# usbboarduino20.net
KiCad netlist of a schematic drawn in EAGLE
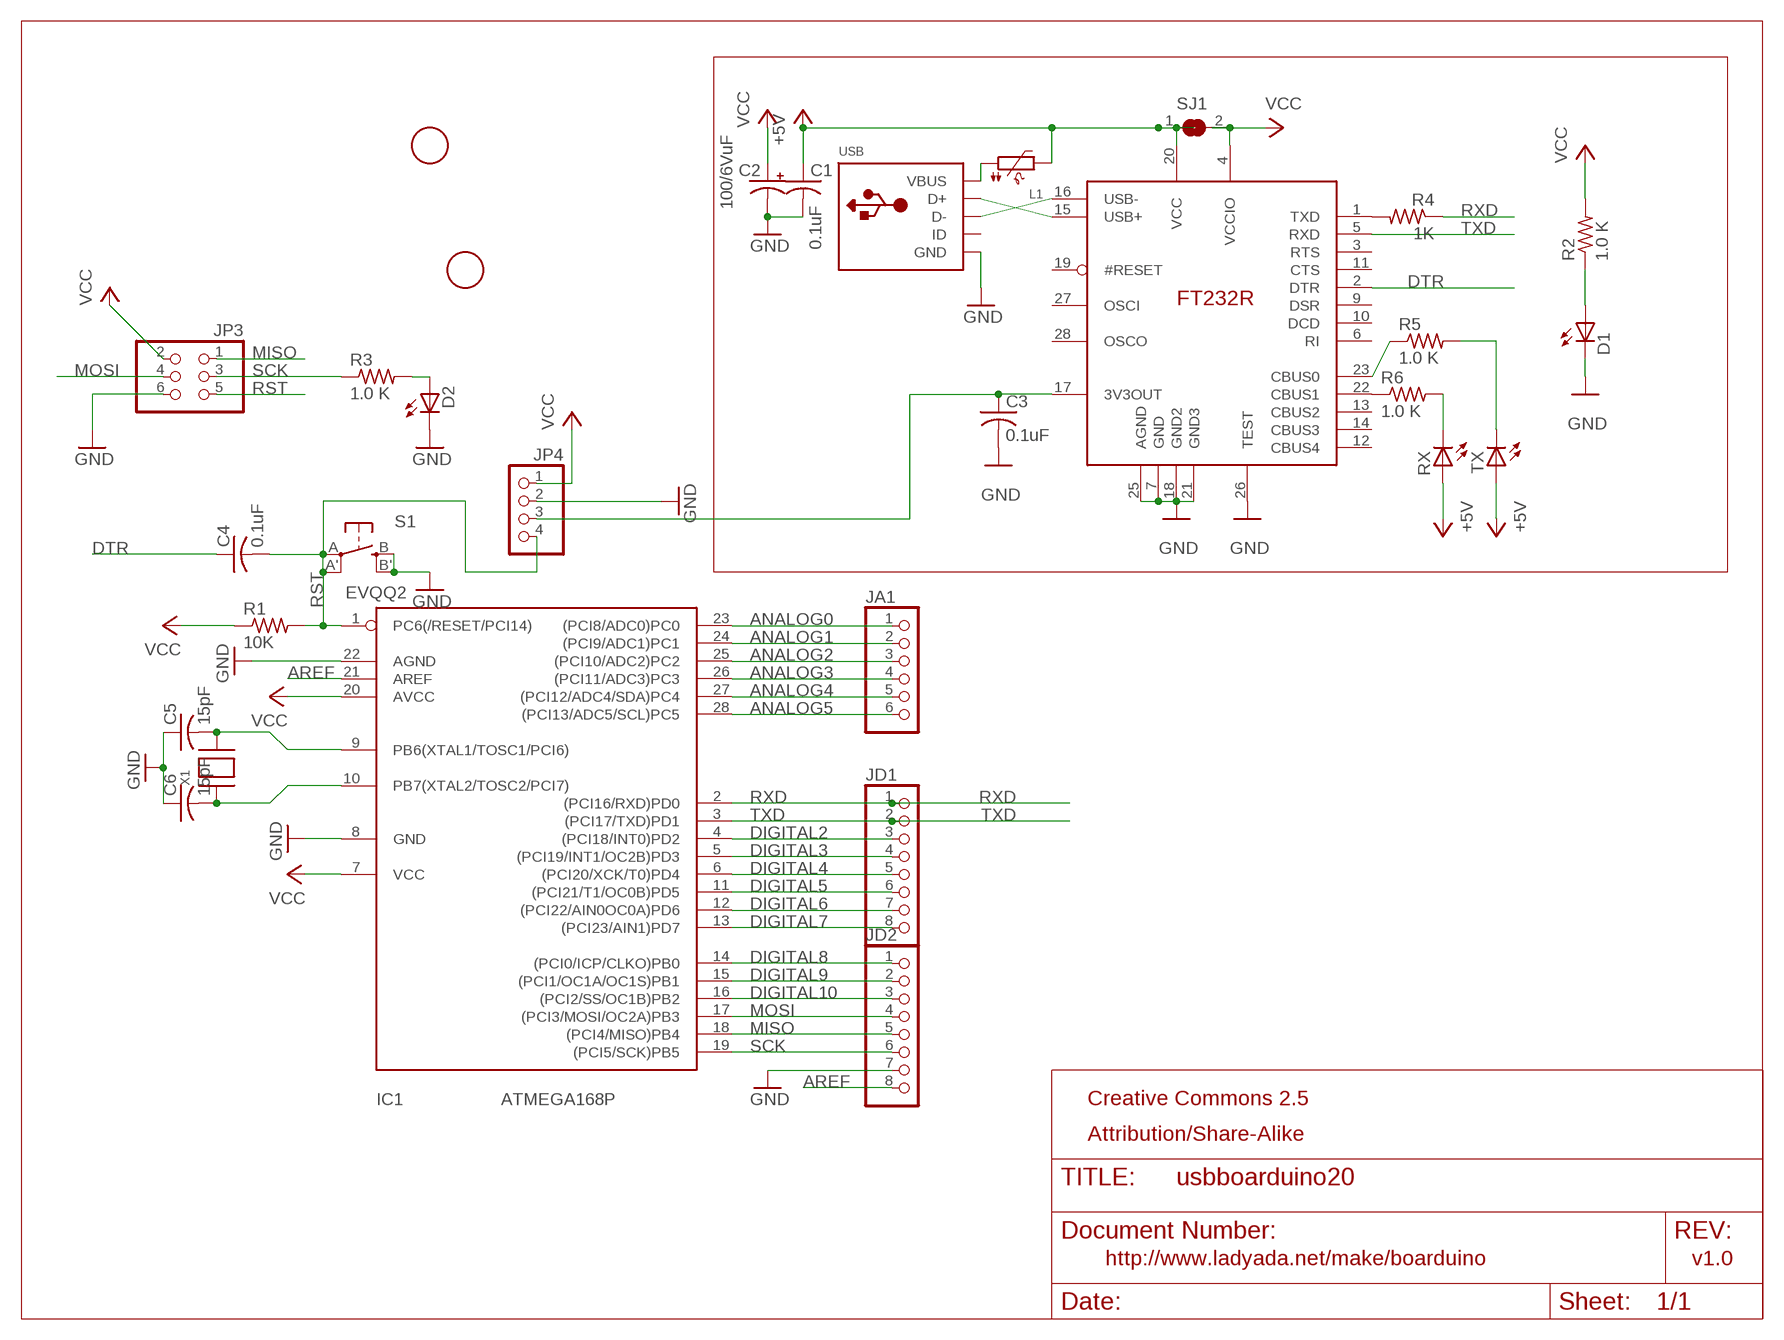
[diagram p0: schematic, sheet 1]

(export (version "E")
  (design (tool "Eeschema 10.0.6"))
  (components
    (comp (ref "C1")
      (value "0.1uF")
      (footprint "eagle-import:C0805K")
      (libsource (lib "eagle-import") (part "C-USC0805K"))
    )
    (comp (ref "C2")
      (value "100/6VuF")
      (footprint "eagle-import:B_3528-21R")
      (libsource (lib "eagle-import") (part "CPOL-USB/3528-21R"))
    )
    (comp (ref "C3")
      (value "0.1uF")
      (footprint "eagle-import:C0805K")
      (libsource (lib "eagle-import") (part "C-USC0805K"))
    )
    (comp (ref "C4")
      (value "0.1uF")
      (footprint "eagle-import:C0805K")
      (libsource (lib "eagle-import") (part "C-USC0805K"))
    )
    (comp (ref "C5")
      (value "15pF")
      (footprint "eagle-import:C0805K")
      (libsource (lib "eagle-import") (part "C-USC0805K"))
    )
    (comp (ref "C6")
      (value "15pF")
      (footprint "eagle-import:C0805K")
      (libsource (lib "eagle-import") (part "C-USC0805K"))
    )
    (comp (ref "D1")
      (value "LEDCHIPLED_0805")
      (footprint "eagle-import:CHIPLED_0805")
      (libsource (lib "eagle-import") (part "LEDCHIPLED_0805"))
    )
    (comp (ref "D2")
      (value "Green")
      (footprint "eagle-import:CHIPLED_0805")
      (libsource (lib "eagle-import") (part "LEDCHIPLED_0805"))
    )
    (comp (ref "IC1")
      (value "ATMEGA168P")
      (footprint "eagle-import:DIL28_3")
      (libsource (lib "eagle-import") (part "ATMEGA168PROUND"))
    )
    (comp (ref "IC2")
      (value "FT232R")
      (footprint "eagle-import:TSSOP28")
      (libsource (lib "eagle-import") (part "FT232R"))
    )
    (comp (ref "JA1")
      (value "PINHD-1X6CB")
      (footprint "eagle-import:1X06-CLEANBIG")
      (libsource (lib "eagle-import") (part "PINHD-1X6CB"))
    )
    (comp (ref "JD1")
      (value "PINHD-1X8CLEANBIG")
      (footprint "eagle-import:1X08-CLEANBIG")
      (libsource (lib "eagle-import") (part "PINHD-1X8CLEANBIG"))
    )
    (comp (ref "JD2")
      (value "PINHD-1X8CLEANBIG")
      (footprint "eagle-import:1X08-CLEANBIG")
      (libsource (lib "eagle-import") (part "PINHD-1X8CLEANBIG"))
    )
    (comp (ref "JP3")
      (value "PINHD-2X3")
      (footprint "eagle-import:2X03")
      (libsource (lib "eagle-import") (part "PINHD-2X3"))
    )
    (comp (ref "JP4")
      (value "PINHD-1X4CB")
      (footprint "eagle-import:1X04-CB")
      (libsource (lib "eagle-import") (part "PINHD-1X4CB"))
    )
    (comp (ref "L1")
      (value "PTC1206")
      (footprint "eagle-import:1206")
      (libsource (lib "eagle-import") (part "PTC1206"))
    )
    (comp (ref "R1")
      (value "10K")
      (footprint "eagle-import:R0805")
      (libsource (lib "eagle-import") (part "R-US_R0805"))
    )
    (comp (ref "R2")
      (value "1.0 K")
      (footprint "eagle-import:R0805")
      (libsource (lib "eagle-import") (part "R-US_R0805"))
    )
    (comp (ref "R3")
      (value "1.0 K")
      (footprint "eagle-import:R0805")
      (libsource (lib "eagle-import") (part "R-US_R0805"))
    )
    (comp (ref "R4")
      (value "1K")
      (footprint "eagle-import:R0805")
      (libsource (lib "eagle-import") (part "R-US_R0805"))
    )
    (comp (ref "R5")
      (value "1.0 K")
      (footprint "eagle-import:R0805")
      (libsource (lib "eagle-import") (part "R-US_R0805"))
    )
    (comp (ref "R6")
      (value "1.0 K")
      (footprint "eagle-import:R0805")
      (libsource (lib "eagle-import") (part "R-US_R0805"))
    )
    (comp (ref "RX")
      (value "Green")
      (footprint "eagle-import:CHIPLED_0805")
      (libsource (lib "eagle-import") (part "LEDCHIPLED_0805"))
    )
    (comp (ref "S1")
      (value "EVQQ2")
      (footprint "eagle-import:EVQ-Q2")
      (libsource (lib "eagle-import") (part "EVQQ2"))
    )
    (comp (ref "SJ1")
      (value "SOLDERJUMPERREFLOW")
      (footprint "eagle-import:SOLDERJUMPER_REFLOW")
      (libsource (lib "eagle-import") (part "SOLDERJUMPERREFLOW"))
    )
    (comp (ref "TX")
      (value "Green")
      (footprint "eagle-import:CHIPLED_0805")
      (libsource (lib "eagle-import") (part "LEDCHIPLED_0805"))
    )
    (comp (ref "U$1")
      (value "FIDUCIAL")
      (footprint "eagle-import:FIDUCIAL_1MM")
      (libsource (lib "eagle-import") (part "FIDUCIAL"))
    )
    (comp (ref "U$2")
      (value "FIDUCIAL")
      (footprint "eagle-import:FIDUCIAL_1MM")
      (libsource (lib "eagle-import") (part "FIDUCIAL"))
    )
    (comp (ref "USB")
      (value "USBMINIB")
      (footprint "eagle-import:USB-MINIB")
      (libsource (lib "eagle-import") (part "USBMINIB"))
    )
    (comp (ref "X1")
      (value "XTALNX5032")
      (footprint "eagle-import:NX5032")
      (libsource (lib "eagle-import") (part "XTALNX5032"))
    )
  )
  (nets
    (net (code "1") (name "+5V") (class "Default")
      (node (ref "C1") (pin "1") (pinfunction "1_1") (pintype "passive"))
      (node (ref "IC2") (pin "20") (pinfunction "VCC_20") (pintype "power_in"))
      (node (ref "L1") (pin "2") (pinfunction "2_2") (pintype "passive"))
      (node (ref "RX") (pin "A") (pinfunction "A_A") (pintype "passive"))
      (node (ref "SJ1") (pin "1") (pinfunction "1_1") (pintype "passive"))
      (node (ref "TX") (pin "A") (pinfunction "A_A") (pintype "passive"))
    )
    (net (code "2") (name "/ANALOG0") (class "Default")
      (node (ref "IC1") (pin "23") (pinfunction "(PCI8/ADC0)PC0_23") (pintype "bidirectional"))
      (node (ref "JA1") (pin "1") (pinfunction "1_1") (pintype "passive"))
    )
    (net (code "3") (name "/ANALOG1") (class "Default")
      (node (ref "IC1") (pin "24") (pinfunction "(PCI9/ADC1)PC1_24") (pintype "bidirectional"))
      (node (ref "JA1") (pin "2") (pinfunction "2_2") (pintype "passive"))
    )
    (net (code "4") (name "/ANALOG2") (class "Default")
      (node (ref "IC1") (pin "25") (pinfunction "(PCI10/ADC2)PC2_25") (pintype "bidirectional"))
      (node (ref "JA1") (pin "3") (pinfunction "3_3") (pintype "passive"))
    )
    (net (code "5") (name "/ANALOG3") (class "Default")
      (node (ref "IC1") (pin "26") (pinfunction "(PCI11/ADC3)PC3_26") (pintype "bidirectional"))
      (node (ref "JA1") (pin "4") (pinfunction "4_4") (pintype "passive"))
    )
    (net (code "6") (name "/ANALOG4") (class "Default")
      (node (ref "IC1") (pin "27") (pinfunction "(PCI12/ADC4/SDA)PC4_27") (pintype "bidirectional"))
      (node (ref "JA1") (pin "5") (pinfunction "5_5") (pintype "passive"))
    )
    (net (code "7") (name "/ANALOG5") (class "Default")
      (node (ref "IC1") (pin "28") (pinfunction "(PCI13/ADC5/SCL)PC5_28") (pintype "bidirectional"))
      (node (ref "JA1") (pin "6") (pinfunction "6_6") (pintype "passive"))
    )
    (net (code "8") (name "/AREF") (class "Default")
      (node (ref "IC1") (pin "21") (pinfunction "AREF_21") (pintype "bidirectional"))
      (node (ref "JD2") (pin "8") (pinfunction "8_8") (pintype "passive"))
    )
    (net (code "9") (name "/DIGITAL2") (class "Default")
      (node (ref "IC1") (pin "4") (pinfunction "(PCI18/INT0)PD2_4") (pintype "bidirectional"))
      (node (ref "JD1") (pin "3") (pinfunction "3_3") (pintype "passive"))
    )
    (net (code "10") (name "/DIGITAL3") (class "Default")
      (node (ref "IC1") (pin "5") (pinfunction "(PCI19/INT1/OC2B)PD3_5") (pintype "bidirectional"))
      (node (ref "JD1") (pin "4") (pinfunction "4_4") (pintype "passive"))
    )
    (net (code "11") (name "/DIGITAL4") (class "Default")
      (node (ref "IC1") (pin "6") (pinfunction "(PCI20/XCK/T0)PD4_6") (pintype "bidirectional"))
      (node (ref "JD1") (pin "5") (pinfunction "5_5") (pintype "passive"))
    )
    (net (code "12") (name "/DIGITAL5") (class "Default")
      (node (ref "IC1") (pin "11") (pinfunction "(PCI21/T1/OC0B)PD5_11") (pintype "bidirectional"))
      (node (ref "JD1") (pin "6") (pinfunction "6_6") (pintype "passive"))
    )
    (net (code "13") (name "/DIGITAL6") (class "Default")
      (node (ref "IC1") (pin "12") (pinfunction "(PCI22/AIN0OC0A)PD6_12") (pintype "bidirectional"))
      (node (ref "JD1") (pin "7") (pinfunction "7_7") (pintype "passive"))
    )
    (net (code "14") (name "/DIGITAL7") (class "Default")
      (node (ref "IC1") (pin "13") (pinfunction "(PCI23/AIN1)PD7_13") (pintype "bidirectional"))
      (node (ref "JD1") (pin "8") (pinfunction "8_8") (pintype "passive"))
    )
    (net (code "15") (name "/DIGITAL8") (class "Default")
      (node (ref "IC1") (pin "14") (pinfunction "(PCI0/ICP/CLKO)PB0_14") (pintype "bidirectional"))
      (node (ref "JD2") (pin "1") (pinfunction "1_1") (pintype "passive"))
    )
    (net (code "16") (name "/DIGITAL9") (class "Default")
      (node (ref "IC1") (pin "15") (pinfunction "(PCI1/OC1A/OC1S)PB1_15") (pintype "bidirectional"))
      (node (ref "JD2") (pin "2") (pinfunction "2_2") (pintype "passive"))
    )
    (net (code "17") (name "/DIGITAL10") (class "Default")
      (node (ref "IC1") (pin "16") (pinfunction "(PCI2/SS/OC1B)PB2_16") (pintype "bidirectional"))
      (node (ref "JD2") (pin "3") (pinfunction "3_3") (pintype "passive"))
    )
    (net (code "18") (name "/DTR") (class "Default")
      (node (ref "C4") (pin "1") (pinfunction "1_1") (pintype "passive"))
      (node (ref "IC2") (pin "2") (pinfunction "DTR_2") (pintype "output"))
    )
    (net (code "19") (name "/MISO") (class "Default")
      (node (ref "IC1") (pin "18") (pinfunction "(PCI4/MISO)PB4_18") (pintype "bidirectional"))
      (node (ref "JD2") (pin "5") (pinfunction "5_5") (pintype "passive"))
      (node (ref "JP3") (pin "1") (pinfunction "1_1") (pintype "passive"))
    )
    (net (code "20") (name "/MOSI") (class "Default")
      (node (ref "IC1") (pin "17") (pinfunction "(PCI3/MOSI/OC2A)PB3_17") (pintype "bidirectional"))
      (node (ref "JD2") (pin "4") (pinfunction "4_4") (pintype "passive"))
      (node (ref "JP3") (pin "4") (pinfunction "4_4") (pintype "passive"))
    )
    (net (code "21") (name "/RST") (class "Default")
      (node (ref "C4") (pin "2") (pinfunction "2_2") (pintype "passive"))
      (node (ref "IC1") (pin "1") (pinfunction "PC6(/RESET/PCI14)_1") (pintype "bidirectional"))
      (node (ref "JP3") (pin "5") (pinfunction "5_5") (pintype "passive"))
      (node (ref "JP4") (pin "4") (pinfunction "4_4") (pintype "passive"))
      (node (ref "R1") (pin "2") (pinfunction "2_2") (pintype "passive"))
      (node (ref "S1") (pin "A") (pinfunction "P_A") (pintype "passive"))
      (node (ref "S1") (pin "A'") (pinfunction "P1_A'") (pintype "passive"))
    )
    (net (code "22") (name "/RXD") (class "Default")
      (node (ref "IC1") (pin "2") (pinfunction "(PCI16/RXD)PD0_2") (pintype "bidirectional"))
      (node (ref "JD1") (pin "1") (pinfunction "1_1") (pintype "passive"))
      (node (ref "R4") (pin "1") (pinfunction "1_1") (pintype "passive"))
    )
    (net (code "23") (name "/SCK") (class "Default")
      (node (ref "IC1") (pin "19") (pinfunction "(PCI5/SCK)PB5_19") (pintype "bidirectional"))
      (node (ref "JD2") (pin "6") (pinfunction "6_6") (pintype "passive"))
      (node (ref "JP3") (pin "3") (pinfunction "3_3") (pintype "passive"))
      (node (ref "R3") (pin "1") (pinfunction "1_1") (pintype "passive"))
    )
    (net (code "24") (name "/TXD") (class "Default")
      (node (ref "IC1") (pin "3") (pinfunction "(PCI17/TXD)PD1_3") (pintype "bidirectional"))
      (node (ref "IC2") (pin "5") (pinfunction "RXD_5") (pintype "input"))
      (node (ref "JD1") (pin "2") (pinfunction "2_2") (pintype "passive"))
    )
    (net (code "25") (name "GND") (class "Default")
      (node (ref "C1") (pin "2") (pinfunction "2_2") (pintype "passive"))
      (node (ref "C2") (pin "-") (pinfunction "-_-") (pintype "passive"))
      (node (ref "C3") (pin "2") (pinfunction "2_2") (pintype "passive"))
      (node (ref "C5") (pin "1") (pinfunction "1_1") (pintype "passive"))
      (node (ref "C6") (pin "1") (pinfunction "1_1") (pintype "passive"))
      (node (ref "D1") (pin "C") (pinfunction "C_C") (pintype "passive"))
      (node (ref "D2") (pin "C") (pinfunction "C_C") (pintype "passive"))
      (node (ref "IC1") (pin "22") (pinfunction "AGND_22") (pintype "bidirectional"))
      (node (ref "IC1") (pin "8") (pinfunction "GND_8") (pintype "bidirectional"))
      (node (ref "IC2") (pin "18") (pinfunction "GND2_18") (pintype "power_in"))
      (node (ref "IC2") (pin "21") (pinfunction "GND3_21") (pintype "power_in"))
      (node (ref "IC2") (pin "25") (pinfunction "AGND_25") (pintype "power_in"))
      (node (ref "IC2") (pin "26") (pinfunction "TEST_26") (pintype "input"))
      (node (ref "IC2") (pin "7") (pinfunction "GND_7") (pintype "power_in"))
      (node (ref "JD2") (pin "7") (pinfunction "7_7") (pintype "passive"))
      (node (ref "JP3") (pin "6") (pinfunction "6_6") (pintype "passive"))
      (node (ref "JP4") (pin "2") (pinfunction "2_2") (pintype "passive"))
      (node (ref "S1") (pin "B") (pinfunction "S_B") (pintype "passive"))
      (node (ref "S1") (pin "B'") (pinfunction "S1_B'") (pintype "passive"))
      (node (ref "USB") (pin "GND") (pinfunction "GND_GND") (pintype "power_in"))
    )
    (net (code "26") (name "Net-(D1-PadA)") (class "Default")
      (node (ref "D1") (pin "A") (pinfunction "A_A") (pintype "passive"))
      (node (ref "R2") (pin "1") (pinfunction "1_1") (pintype "passive"))
    )
    (net (code "27") (name "Net-(D2-PadA)") (class "Default")
      (node (ref "D2") (pin "A") (pinfunction "A_A") (pintype "passive"))
      (node (ref "R3") (pin "2") (pinfunction "2_2") (pintype "passive"))
    )
    (net (code "28") (name "Net-(IC1-PB6(XTAL1{slash}TOSC1{slash}PCI6))") (class "Default")
      (node (ref "C5") (pin "2") (pinfunction "2_2") (pintype "passive"))
      (node (ref "IC1") (pin "9") (pinfunction "PB6(XTAL1/TOSC1/PCI6)_9") (pintype "bidirectional"))
      (node (ref "X1") (pin "P$2") (pinfunction "P$2_P$2") (pintype "bidirectional"))
    )
    (net (code "29") (name "Net-(IC1-PB7(XTAL2{slash}TOSC2{slash}PCI7))") (class "Default")
      (node (ref "C6") (pin "2") (pinfunction "2_2") (pintype "passive"))
      (node (ref "IC1") (pin "10") (pinfunction "PB7(XTAL2/TOSC2/PCI7)_10") (pintype "bidirectional"))
      (node (ref "X1") (pin "P$1") (pinfunction "P$1_P$1") (pintype "bidirectional"))
    )
    (net (code "30") (name "Net-(IC2-3V3OUT)") (class "Default")
      (node (ref "C3") (pin "1") (pinfunction "1_1") (pintype "passive"))
      (node (ref "IC2") (pin "17") (pinfunction "3V3OUT_17") (pintype "output"))
      (node (ref "JP4") (pin "3") (pinfunction "3_3") (pintype "passive"))
    )
    (net (code "31") (name "Net-(IC2-CBUS0)") (class "Default")
      (node (ref "IC2") (pin "23") (pinfunction "CBUS0_23") (pintype "bidirectional"))
      (node (ref "R5") (pin "1") (pinfunction "1_1") (pintype "passive"))
    )
    (net (code "32") (name "Net-(IC2-CBUS1)") (class "Default")
      (node (ref "IC2") (pin "22") (pinfunction "CBUS1_22") (pintype "bidirectional"))
      (node (ref "R6") (pin "1") (pinfunction "1_1") (pintype "passive"))
    )
    (net (code "33") (name "Net-(IC2-TXD)") (class "Default")
      (node (ref "IC2") (pin "1") (pinfunction "TXD_1") (pintype "output"))
      (node (ref "R4") (pin "2") (pinfunction "2_2") (pintype "passive"))
    )
    (net (code "34") (name "Net-(IC2-USB+)") (class "Default")
      (node (ref "IC2") (pin "15") (pinfunction "USB+_15") (pintype "bidirectional"))
      (node (ref "USB") (pin "D+") (pinfunction "D+_D+") (pintype "bidirectional"))
    )
    (net (code "35") (name "Net-(IC2-USB-)") (class "Default")
      (node (ref "IC2") (pin "16") (pinfunction "USB-_16") (pintype "bidirectional"))
      (node (ref "USB") (pin "D-") (pinfunction "D-_D-") (pintype "bidirectional"))
    )
    (net (code "36") (name "Net-(L1-Pad1)") (class "Default")
      (node (ref "L1") (pin "1") (pinfunction "1_1") (pintype "passive"))
      (node (ref "USB") (pin "VBUS") (pinfunction "VBUS_VBUS") (pintype "power_in"))
    )
    (net (code "37") (name "Net-(R5-Pad2)") (class "Default")
      (node (ref "R5") (pin "2") (pinfunction "2_2") (pintype "passive"))
      (node (ref "TX") (pin "C") (pinfunction "C_C") (pintype "passive"))
    )
    (net (code "38") (name "Net-(R6-Pad2)") (class "Default")
      (node (ref "R6") (pin "2") (pinfunction "2_2") (pintype "passive"))
      (node (ref "RX") (pin "C") (pinfunction "C_C") (pintype "passive"))
    )
    (net (code "39") (name "VCC") (class "Default")
      (node (ref "C2") (pin "+") (pinfunction "+_+") (pintype "passive"))
      (node (ref "IC1") (pin "20") (pinfunction "AVCC_20") (pintype "bidirectional"))
      (node (ref "IC1") (pin "7") (pinfunction "VCC_7") (pintype "bidirectional"))
      (node (ref "IC2") (pin "4") (pinfunction "VCCIO_4") (pintype "power_in"))
      (node (ref "JP3") (pin "2") (pinfunction "2_2") (pintype "passive"))
      (node (ref "JP4") (pin "1") (pinfunction "1_1") (pintype "passive"))
      (node (ref "R1") (pin "1") (pinfunction "1_1") (pintype "passive"))
      (node (ref "R2") (pin "2") (pinfunction "2_2") (pintype "passive"))
      (node (ref "SJ1") (pin "2") (pinfunction "2_2") (pintype "passive"))
    )
    (net (code "40") (name "unconnected-(IC2-#RESET-Pad19)") (class "Default")
      (node (ref "IC2") (pin "19") (pinfunction "#RESET_19") (pintype "input"))
    )
    (net (code "41") (name "unconnected-(IC2-CBUS2-Pad13)") (class "Default")
      (node (ref "IC2") (pin "13") (pinfunction "CBUS2_13") (pintype "bidirectional"))
    )
    (net (code "42") (name "unconnected-(IC2-CBUS3-Pad14)") (class "Default")
      (node (ref "IC2") (pin "14") (pinfunction "CBUS3_14") (pintype "bidirectional"))
    )
    (net (code "43") (name "unconnected-(IC2-CBUS4-Pad12)") (class "Default")
      (node (ref "IC2") (pin "12") (pinfunction "CBUS4_12") (pintype "bidirectional"))
    )
    (net (code "44") (name "unconnected-(IC2-CTS-Pad11)") (class "Default")
      (node (ref "IC2") (pin "11") (pinfunction "CTS_11") (pintype "input"))
    )
    (net (code "45") (name "unconnected-(IC2-DCD-Pad10)") (class "Default")
      (node (ref "IC2") (pin "10") (pinfunction "DCD_10") (pintype "input"))
    )
    (net (code "46") (name "unconnected-(IC2-DSR-Pad9)") (class "Default")
      (node (ref "IC2") (pin "9") (pinfunction "DSR_9") (pintype "input"))
    )
    (net (code "47") (name "unconnected-(IC2-OSCI-Pad27)") (class "Default")
      (node (ref "IC2") (pin "27") (pinfunction "OSCI_27") (pintype "input"))
    )
    (net (code "48") (name "unconnected-(IC2-OSCO-Pad28)") (class "Default")
      (node (ref "IC2") (pin "28") (pinfunction "OSCO_28") (pintype "output"))
    )
    (net (code "49") (name "unconnected-(IC2-RI-Pad6)") (class "Default")
      (node (ref "IC2") (pin "6") (pinfunction "RI_6") (pintype "input"))
    )
    (net (code "50") (name "unconnected-(IC2-RTS-Pad3)") (class "Default")
      (node (ref "IC2") (pin "3") (pinfunction "RTS_3") (pintype "output"))
    )
    (net (code "51") (name "unconnected-(USB-PadID)") (class "Default")
      (node (ref "USB") (pin "ID") (pinfunction "ID_ID") (pintype "bidirectional"))
    )
  )
)
